# Voltage_conversion.net
KiCad netlist of a schematic drawn in Altium Designer
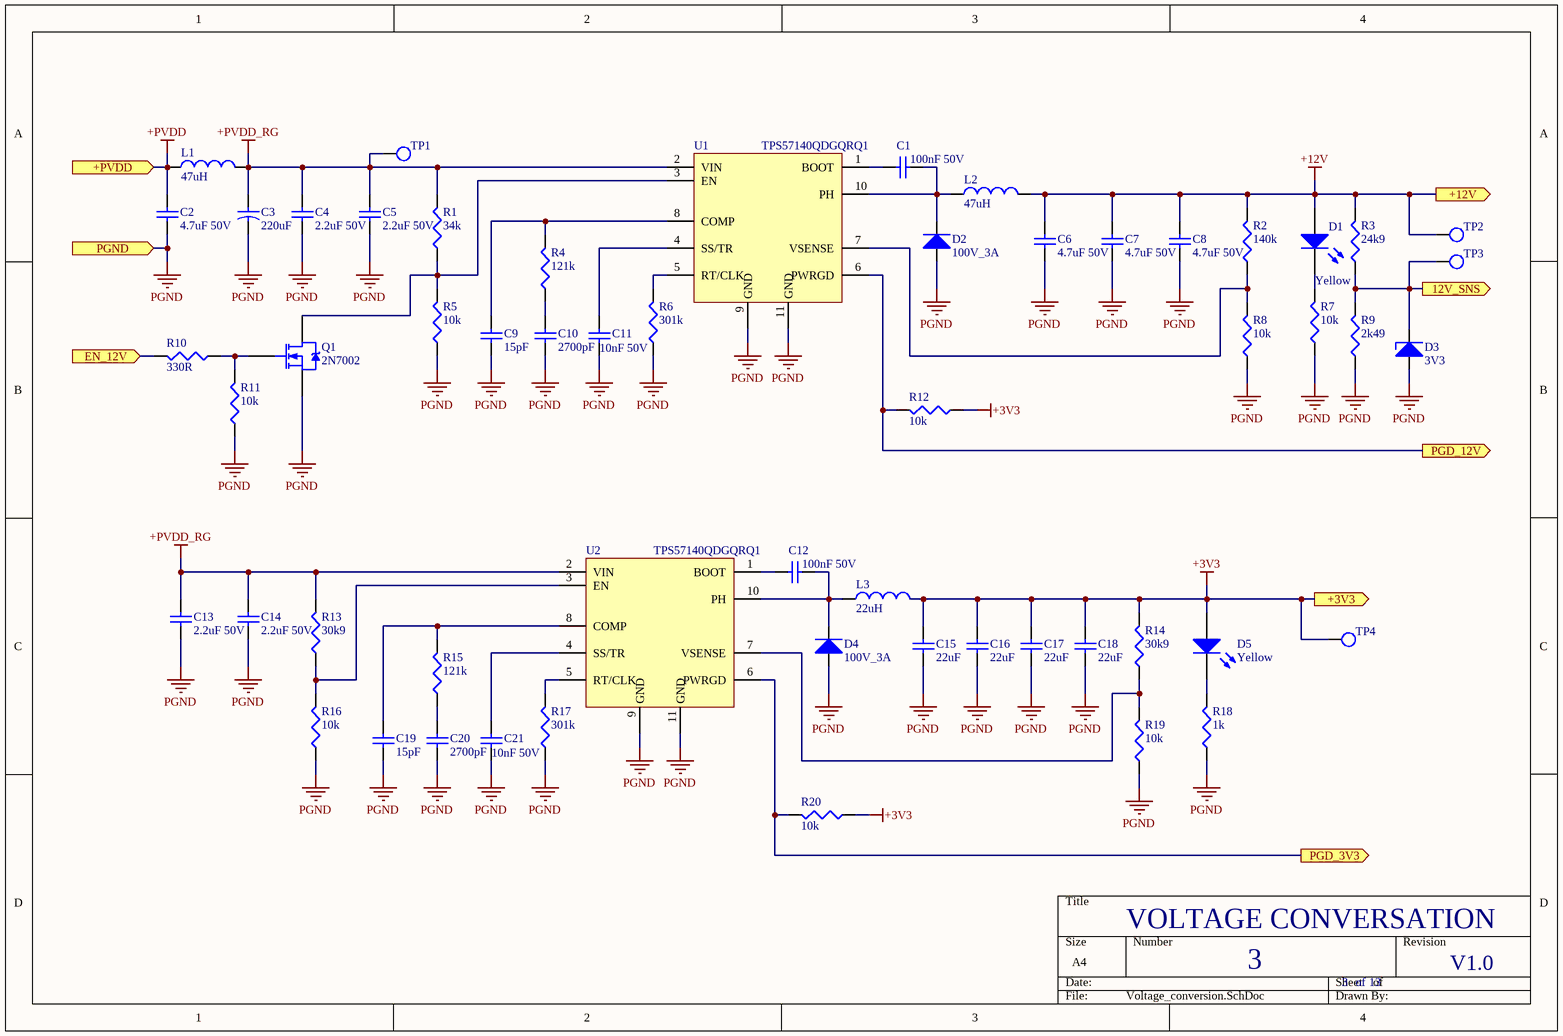
[diagram p0: Voltage_conversion.SchDoc]

(export (version "E")
  (design (tool "Eeschema 10.0.6"))
  (components
    (comp (ref "C1")
      (value "100nF 50V")
      (footprint "CAP0603")
      (description "CAP CER 0.1UF 50V X7R 0603")
      (libsource (lib "CAP_Library") (part "CAP0603_100nF"))
    )
    (comp (ref "C2")
      (value "4.7uF 50V")
      (footprint "CAP1206")
      (description "CAP CER 4.7UF 50V %20 X7R 1206")
      (libsource (lib "CAP_Library") (part "CAP1206_4.7uF"))
    )
    (comp (ref "C3")
      (value "220uF")
      (footprint "CAP_RADIAL_SMD_10x10")
      (description "CAP ALUM 220UF 20% 50V SMD")
      (libsource (lib "CAP_Library") (part "CAP_RADIAL_EEE-FK1H221GP"))
    )
    (comp (ref "C4")
      (value "2.2uF 50V")
      (footprint "CAP1206")
      (description "CAP CER 2.2UF 50V X7R 1206")
      (libsource (lib "CAP_Library") (part "CAP1206_2.2uF_50V"))
    )
    (comp (ref "C5")
      (value "2.2uF 50V")
      (footprint "CAP1206")
      (description "CAP CER 2.2UF 50V X7R 1206")
      (libsource (lib "CAP_Library") (part "CAP1206_2.2uF_50V"))
    )
    (comp (ref "C6")
      (value "4.7uF 50V")
      (footprint "CAP1206")
      (description "CAP CER 4.7UF 50V %20 X7R 1206")
      (libsource (lib "CAP_Library") (part "CAP1206_4.7uF"))
    )
    (comp (ref "C7")
      (value "4.7uF 50V")
      (footprint "CAP1206")
      (description "CAP CER 4.7UF 50V %20 X7R 1206")
      (libsource (lib "CAP_Library") (part "CAP1206_4.7uF"))
    )
    (comp (ref "C8")
      (value "4.7uF 50V")
      (footprint "CAP1206")
      (description "CAP CER 4.7UF 50V %20 X7R 1206")
      (libsource (lib "CAP_Library") (part "CAP1206_4.7uF"))
    )
    (comp (ref "C9")
      (value "15pF")
      (footprint "CAP0603")
      (description "CAP CER 15PF 50V C0G/NP0 0603")
      (libsource (lib "CAP_Library") (part "CAP0603_15pF"))
    )
    (comp (ref "C10")
      (value "2700pF")
      (footprint "CAP0603")
      (description "CAP CER 1200PF 50V X7R 0603")
      (libsource (lib "CAP_Library") (part "CAP0603_2700pF"))
    )
    (comp (ref "C11")
      (value "10nF 50V")
      (footprint "CAP0603")
      (description "CAP CER 10nF 50V X7R 0603")
      (libsource (lib "CAP_Library") (part "CAP0603_10nF"))
    )
    (comp (ref "C12")
      (value "100nF 50V")
      (footprint "CAP0603")
      (description "CAP CER 0.1UF 50V X7R 0603")
      (libsource (lib "CAP_Library") (part "CAP0603_100nF"))
    )
    (comp (ref "C13")
      (value "2.2uF 50V")
      (footprint "CAP1206")
      (description "CAP CER 2.2UF 50V X7R 1206")
      (libsource (lib "CAP_Library") (part "CAP1206_2.2uF_50V"))
    )
    (comp (ref "C14")
      (value "2.2uF 50V")
      (footprint "CAP1206")
      (description "CAP CER 2.2UF 50V X7R 1206")
      (libsource (lib "CAP_Library") (part "CAP1206_2.2uF_50V"))
    )
    (comp (ref "C15")
      (value "22uF")
      (footprint "CAP1206")
      (description "CAP CER 22UF 16V X6S 1206")
      (libsource (lib "CAP_Library") (part "CAP1206_22uF_16V"))
    )
    (comp (ref "C16")
      (value "22uF")
      (footprint "CAP1206")
      (description "CAP CER 22UF 16V X6S 1206")
      (libsource (lib "CAP_Library") (part "CAP1206_22uF_16V"))
    )
    (comp (ref "C17")
      (value "22uF")
      (footprint "CAP1206")
      (description "CAP CER 22UF 16V X6S 1206")
      (libsource (lib "CAP_Library") (part "CAP1206_22uF_16V"))
    )
    (comp (ref "C18")
      (value "22uF")
      (footprint "CAP1206")
      (description "CAP CER 22UF 16V X6S 1206")
      (libsource (lib "CAP_Library") (part "CAP1206_22uF_16V"))
    )
    (comp (ref "C19")
      (value "15pF")
      (footprint "CAP0603")
      (description "CAP CER 15PF 50V C0G/NP0 0603")
      (libsource (lib "CAP_Library") (part "CAP0603_15pF"))
    )
    (comp (ref "C20")
      (value "2700pF")
      (footprint "CAP0603")
      (description "CAP CER 1200PF 50V X7R 0603")
      (libsource (lib "CAP_Library") (part "CAP0603_2700pF"))
    )
    (comp (ref "C21")
      (value "10nF 50V")
      (footprint "CAP0603")
      (description "CAP CER 10nF 50V X7R 0603")
      (libsource (lib "CAP_Library") (part "CAP0603_10nF"))
    )
    (comp (ref "D1")
      (value "Yellow")
      (footprint "LED0603")
      (description "LED YELLOW CLEAR 0603 SMD")
      (libsource (lib "MISC_Library") (part "LED0603_YELLOW"))
    )
    (comp (ref "D2")
      (value "100V_3A")
      (footprint "DO-221A")
      (description "DIODE FRED 100V 3A DO-221AD")
      (libsource (lib "DIODE_Library") (part "FRED_VS-3EYH01-M3/H_100V_3A"))
    )
    (comp (ref "D3")
      (value "3V3")
      (footprint "SOD323")
      (description "DIODE ZENER 3.3V 300MW SOD323")
      (libsource (lib "DIODE_Library") (part "ZENER_3V3_MM3Z3V3T1G"))
    )
    (comp (ref "D4")
      (value "100V_3A")
      (footprint "DO-221A")
      (description "DIODE FRED 100V 3A DO-221AD")
      (libsource (lib "DIODE_Library") (part "FRED_VS-3EYH01-M3/H_100V_3A"))
    )
    (comp (ref "D5")
      (value "Yellow")
      (footprint "LED0603")
      (description "LED YELLOW CLEAR 0603 SMD")
      (libsource (lib "MISC_Library") (part "LED0603_YELLOW"))
    )
    (comp (ref "L1")
      (value "47uH")
      (footprint "IND_SRR1208")
      (description "FIXED IND 47UH 2.9A 80 MOHM SMD")
      (libsource (lib "IND_Library") (part "IND_SRR1280-470M"))
    )
    (comp (ref "L2")
      (value "47uH")
      (footprint "IND_SRR1208")
      (description "FIXED IND 47UH 2.9A 80 MOHM SMD")
      (libsource (lib "IND_Library") (part "IND_SRR1280-470M"))
    )
    (comp (ref "L3")
      (value "22uH")
      (footprint "IND_VLS")
      (description "FIXED IND 22UH 1.9A 105MOHM SMD")
      (libsource (lib "IND_Library") (part "IND_VLS6045EX-220M-H"))
    )
    (comp (ref "Q1")
      (value "2N7002")
      (footprint "SOT23_2N7002")
      (description "MOSFET N-CH 60V 0.36A SOT-23")
      (libsource (lib "Mosfet_Library") (part "2N7002P,215_NMOS_60V"))
    )
    (comp (ref "R1")
      (value "34k")
      (footprint "RES0603")
      (description "RES SMD 34K OHM 1% 1/10W 0603")
      (libsource (lib "RES_Library") (part "RES0603_34k"))
    )
    (comp (ref "R2")
      (value "140k")
      (footprint "RES0603")
      (description "RES 1470 OHM 1% 1/10W 0603")
      (libsource (lib "RES_Library") (part "RES0603_140k"))
    )
    (comp (ref "R3")
      (value "24k9")
      (footprint "RES0603")
      (description "RES SMD 24.9K OHM 1% 1/10W 0603")
      (libsource (lib "RES_Library") (part "RES0603_24k9"))
    )
    (comp (ref "R4")
      (value "121k")
      (footprint "RES0603")
      (description "RES 121K OHM 1% 1/10W 0603")
      (libsource (lib "RES_Library") (part "RES0603_121k"))
    )
    (comp (ref "R5")
      (value "10k")
      (footprint "RES0603")
      (description "RES SMD 10K OHM 5% 1/10W 0603")
      (libsource (lib "RES_Library") (part "RES0603_10k"))
    )
    (comp (ref "R6")
      (value "301k")
      (footprint "RES0603")
      (description "RES SMD 301K OHM 1% 1/10W 0603")
      (libsource (lib "RES_Library") (part "RES0603_301k"))
    )
    (comp (ref "R7")
      (value "10k")
      (footprint "RES0603")
      (description "RES SMD 10K OHM 5% 1/10W 0603")
      (libsource (lib "RES_Library") (part "RES0603_10k"))
    )
    (comp (ref "R8")
      (value "10k")
      (footprint "RES0603")
      (description "RES SMD 10K OHM 5% 1/10W 0603")
      (libsource (lib "RES_Library") (part "RES0603_10k"))
    )
    (comp (ref "R9")
      (value "2k49")
      (footprint "RES0603")
      (description "RES 2.49K OHM 1% 1/10W 0603")
      (libsource (lib "RES_Library") (part "RES0603_2k49"))
    )
    (comp (ref "R10")
      (value "330R")
      (footprint "RES0603")
      (description "RES 330 OHM 1% 1/10W 0603")
      (libsource (lib "RES_Library") (part "RES0603_330R"))
    )
    (comp (ref "R11")
      (value "10k")
      (footprint "RES0603")
      (description "RES SMD 10K OHM 5% 1/10W 0603")
      (libsource (lib "RES_Library") (part "RES0603_10k"))
    )
    (comp (ref "R12")
      (value "10k")
      (footprint "RES0603")
      (description "RES SMD 10K OHM 5% 1/10W 0603")
      (libsource (lib "RES_Library") (part "RES0603_10k"))
    )
    (comp (ref "R13")
      (value "30k9")
      (footprint "RES0603")
      (description "RES SMD 30K9 OHM 1% 1/10W 0603")
      (libsource (lib "RES_Library") (part "RES0603_30k9"))
    )
    (comp (ref "R14")
      (value "30k9")
      (footprint "RES0603")
      (description "RES SMD 30K9 OHM 1% 1/10W 0603")
      (libsource (lib "RES_Library") (part "RES0603_30k9"))
    )
    (comp (ref "R15")
      (value "121k")
      (footprint "RES0603")
      (description "RES 121K OHM 1% 1/10W 0603")
      (libsource (lib "RES_Library") (part "RES0603_121k"))
    )
    (comp (ref "R16")
      (value "10k")
      (footprint "RES0603")
      (description "RES SMD 10K OHM 5% 1/10W 0603")
      (libsource (lib "RES_Library") (part "RES0603_10k"))
    )
    (comp (ref "R17")
      (value "301k")
      (footprint "RES0603")
      (description "RES SMD 301K OHM 1% 1/10W 0603")
      (libsource (lib "RES_Library") (part "RES0603_301k"))
    )
    (comp (ref "R18")
      (value "1k")
      (footprint "RES0603")
      (description "RES SMD 1K OHM 1% 1/10W 0603")
      (libsource (lib "RES_Library") (part "RES0603_1k"))
    )
    (comp (ref "R19")
      (value "10k")
      (footprint "RES0603")
      (description "RES SMD 10K OHM 5% 1/10W 0603")
      (libsource (lib "RES_Library") (part "RES0603_10k"))
    )
    (comp (ref "R20")
      (value "10k")
      (footprint "RES0603")
      (description "RES SMD 10K OHM 5% 1/10W 0603")
      (libsource (lib "RES_Library") (part "RES0603_10k"))
    )
    (comp (ref "TP1")
      (value "TEST_POINT")
      (footprint "TEST_POINT_TH")
      (libsource (lib "MISC_Library") (part "TEST_POINT"))
    )
    (comp (ref "TP2")
      (value "TEST_POINT")
      (footprint "TEST_POINT_TH")
      (libsource (lib "MISC_Library") (part "TEST_POINT"))
    )
    (comp (ref "TP3")
      (value "TEST_POINT")
      (footprint "TEST_POINT_TH")
      (libsource (lib "MISC_Library") (part "TEST_POINT"))
    )
    (comp (ref "TP4")
      (value "TEST_POINT")
      (footprint "TEST_POINT_TH")
      (libsource (lib "MISC_Library") (part "TEST_POINT"))
    )
    (comp (ref "U1")
      (value "1.5A")
      (footprint "MSOP_EP")
      (description "IC REG BUCK ADJ 1.5A 10MSOP")
      (fields (field (name "P/N") "TPS57140QDGQRQ1"))
      (libsource (lib "IC_Library") (part "REG_SMPS_TPS57140QDGQRQ1"))
    )
    (comp (ref "U2")
      (value "1.5A")
      (footprint "MSOP_EP")
      (description "IC REG BUCK ADJ 1.5A 10MSOP")
      (fields (field (name "P/N") "TPS57140QDGQRQ1"))
      (libsource (lib "IC_Library") (part "REG_SMPS_TPS57140QDGQRQ1"))
    )
  )
  (nets
    (net (code "1") (name "+3V3") (class "Default")
      (node (ref "C15") (pin "2") (pinfunction "2_2") (pintype "passive"))
      (node (ref "C16") (pin "2") (pinfunction "2_2") (pintype "passive"))
      (node (ref "C17") (pin "2") (pinfunction "2_2") (pintype "passive"))
      (node (ref "C18") (pin "2") (pinfunction "2_2") (pintype "passive"))
      (node (ref "D5") (pin "1") (pinfunction "A_1") (pintype "passive"))
      (node (ref "L3") (pin "2") (pinfunction "2_2") (pintype "passive"))
      (node (ref "R12") (pin "1") (pinfunction "1_1") (pintype "passive"))
      (node (ref "R14") (pin "2") (pinfunction "2_2") (pintype "passive"))
      (node (ref "R20") (pin "1") (pinfunction "1_1") (pintype "passive"))
      (node (ref "TP4") (pin "1") (pinfunction "1_1") (pintype "passive"))
    )
    (net (code "2") (name "+12V") (class "Default")
      (node (ref "C6") (pin "2") (pinfunction "2_2") (pintype "passive"))
      (node (ref "C7") (pin "2") (pinfunction "2_2") (pintype "passive"))
      (node (ref "C8") (pin "2") (pinfunction "2_2") (pintype "passive"))
      (node (ref "D1") (pin "1") (pinfunction "A_1") (pintype "passive"))
      (node (ref "L2") (pin "2") (pinfunction "2_2") (pintype "passive"))
      (node (ref "R2") (pin "2") (pinfunction "2_2") (pintype "passive"))
      (node (ref "R3") (pin "2") (pinfunction "2_2") (pintype "passive"))
      (node (ref "TP2") (pin "1") (pinfunction "1_1") (pintype "passive"))
    )
    (net (code "3") (name "+PVDD") (class "Default")
      (node (ref "C2") (pin "2") (pinfunction "2_2") (pintype "passive"))
      (node (ref "L1") (pin "1") (pinfunction "1_1") (pintype "passive"))
    )
    (net (code "4") (name "+PVDD_RG") (class "Default")
      (node (ref "C13") (pin "2") (pinfunction "2_2") (pintype "passive"))
      (node (ref "C14") (pin "2") (pinfunction "2_2") (pintype "passive"))
      (node (ref "C3") (pin "1") (pinfunction "1_1") (pintype "passive"))
      (node (ref "C4") (pin "2") (pinfunction "2_2") (pintype "passive"))
      (node (ref "C5") (pin "2") (pinfunction "2_2") (pintype "passive"))
      (node (ref "L1") (pin "2") (pinfunction "2_2") (pintype "passive"))
      (node (ref "R1") (pin "2") (pinfunction "2_2") (pintype "passive"))
      (node (ref "R13") (pin "2") (pinfunction "2_2") (pintype "passive"))
      (node (ref "TP1") (pin "1") (pinfunction "1_1") (pintype "passive"))
      (node (ref "U1") (pin "2") (pinfunction "VIN_2") (pintype "passive"))
      (node (ref "U2") (pin "2") (pinfunction "VIN_2") (pintype "passive"))
    )
    (net (code "5") (name "/12V_SNS") (class "Default")
      (node (ref "D3") (pin "1") (pinfunction "K_1") (pintype "passive"))
      (node (ref "R3") (pin "1") (pinfunction "1_1") (pintype "passive"))
      (node (ref "R9") (pin "2") (pinfunction "2_2") (pintype "passive"))
      (node (ref "TP3") (pin "1") (pinfunction "1_1") (pintype "passive"))
    )
    (net (code "6") (name "/EN_12V") (class "Default")
      (node (ref "R10") (pin "2") (pinfunction "2_2") (pintype "passive"))
    )
    (net (code "7") (name "/PGD_3V3") (class "Default")
      (node (ref "R20") (pin "2") (pinfunction "2_2") (pintype "passive"))
      (node (ref "U2") (pin "6") (pinfunction "PWRGD_6") (pintype "passive"))
    )
    (net (code "8") (name "/PGD_12V") (class "Default")
      (node (ref "R12") (pin "2") (pinfunction "2_2") (pintype "passive"))
      (node (ref "U1") (pin "6") (pinfunction "PWRGD_6") (pintype "passive"))
    )
    (net (code "9") (name "Net-(C10-Pad2)") (class "Default")
      (node (ref "C10") (pin "2") (pinfunction "2_2") (pintype "passive"))
      (node (ref "R4") (pin "1") (pinfunction "1_1") (pintype "passive"))
    )
    (net (code "10") (name "Net-(C20-Pad2)") (class "Default")
      (node (ref "C20") (pin "2") (pinfunction "2_2") (pintype "passive"))
      (node (ref "R15") (pin "1") (pinfunction "1_1") (pintype "passive"))
    )
    (net (code "11") (name "Net-(D1-K)") (class "Default")
      (node (ref "D1") (pin "2") (pinfunction "K_2") (pintype "passive"))
      (node (ref "R7") (pin "2") (pinfunction "2_2") (pintype "passive"))
    )
    (net (code "12") (name "Net-(D2-K)") (class "Default")
      (node (ref "C1") (pin "1") (pinfunction "1_1") (pintype "passive"))
      (node (ref "D2") (pin "1") (pinfunction "K_1") (pintype "passive"))
      (node (ref "L2") (pin "1") (pinfunction "1_1") (pintype "passive"))
      (node (ref "U1") (pin "10") (pinfunction "PH_10") (pintype "passive"))
    )
    (net (code "13") (name "Net-(D4-K)") (class "Default")
      (node (ref "C12") (pin "1") (pinfunction "1_1") (pintype "passive"))
      (node (ref "D4") (pin "1") (pinfunction "K_1") (pintype "passive"))
      (node (ref "L3") (pin "1") (pinfunction "1_1") (pintype "passive"))
      (node (ref "U2") (pin "10") (pinfunction "PH_10") (pintype "passive"))
    )
    (net (code "14") (name "Net-(D5-K)") (class "Default")
      (node (ref "D5") (pin "2") (pinfunction "K_2") (pintype "passive"))
      (node (ref "R18") (pin "2") (pinfunction "2_2") (pintype "passive"))
    )
    (net (code "15") (name "Net-(Q1-D)") (class "Default")
      (node (ref "Q1") (pin "3") (pinfunction "D_3") (pintype "passive"))
      (node (ref "R1") (pin "1") (pinfunction "1_1") (pintype "passive"))
      (node (ref "R5") (pin "2") (pinfunction "2_2") (pintype "passive"))
      (node (ref "U1") (pin "3") (pinfunction "EN_3") (pintype "passive"))
    )
    (net (code "16") (name "Net-(Q1-G)") (class "Default")
      (node (ref "Q1") (pin "1") (pinfunction "G_1") (pintype "passive"))
      (node (ref "R10") (pin "1") (pinfunction "1_1") (pintype "passive"))
      (node (ref "R11") (pin "2") (pinfunction "2_2") (pintype "passive"))
    )
    (net (code "17") (name "Net-(U1-BOOT)") (class "Default")
      (node (ref "C1") (pin "2") (pinfunction "2_2") (pintype "passive"))
      (node (ref "U1") (pin "1") (pinfunction "BOOT_1") (pintype "passive"))
    )
    (net (code "18") (name "Net-(U1-COMP)") (class "Default")
      (node (ref "C9") (pin "2") (pinfunction "2_2") (pintype "passive"))
      (node (ref "R4") (pin "2") (pinfunction "2_2") (pintype "passive"))
      (node (ref "U1") (pin "8") (pinfunction "COMP_8") (pintype "passive"))
    )
    (net (code "19") (name "Net-(U1-RT{slash}CLK)") (class "Default")
      (node (ref "R6") (pin "2") (pinfunction "2_2") (pintype "passive"))
      (node (ref "U1") (pin "5") (pinfunction "RT/CLK_5") (pintype "passive"))
    )
    (net (code "20") (name "Net-(U1-SS{slash}TR)") (class "Default")
      (node (ref "C11") (pin "2") (pinfunction "2_2") (pintype "passive"))
      (node (ref "U1") (pin "4") (pinfunction "SS/TR_4") (pintype "passive"))
    )
    (net (code "21") (name "Net-(U1-VSENSE)") (class "Default")
      (node (ref "R2") (pin "1") (pinfunction "1_1") (pintype "passive"))
      (node (ref "R8") (pin "2") (pinfunction "2_2") (pintype "passive"))
      (node (ref "U1") (pin "7") (pinfunction "VSENSE_7") (pintype "passive"))
    )
    (net (code "22") (name "Net-(U2-BOOT)") (class "Default")
      (node (ref "C12") (pin "2") (pinfunction "2_2") (pintype "passive"))
      (node (ref "U2") (pin "1") (pinfunction "BOOT_1") (pintype "passive"))
    )
    (net (code "23") (name "Net-(U2-COMP)") (class "Default")
      (node (ref "C19") (pin "2") (pinfunction "2_2") (pintype "passive"))
      (node (ref "R15") (pin "2") (pinfunction "2_2") (pintype "passive"))
      (node (ref "U2") (pin "8") (pinfunction "COMP_8") (pintype "passive"))
    )
    (net (code "24") (name "Net-(U2-EN)") (class "Default")
      (node (ref "R13") (pin "1") (pinfunction "1_1") (pintype "passive"))
      (node (ref "R16") (pin "2") (pinfunction "2_2") (pintype "passive"))
      (node (ref "U2") (pin "3") (pinfunction "EN_3") (pintype "passive"))
    )
    (net (code "25") (name "Net-(U2-RT{slash}CLK)") (class "Default")
      (node (ref "R17") (pin "2") (pinfunction "2_2") (pintype "passive"))
      (node (ref "U2") (pin "5") (pinfunction "RT/CLK_5") (pintype "passive"))
    )
    (net (code "26") (name "Net-(U2-SS{slash}TR)") (class "Default")
      (node (ref "C21") (pin "2") (pinfunction "2_2") (pintype "passive"))
      (node (ref "U2") (pin "4") (pinfunction "SS/TR_4") (pintype "passive"))
    )
    (net (code "27") (name "Net-(U2-VSENSE)") (class "Default")
      (node (ref "R14") (pin "1") (pinfunction "1_1") (pintype "passive"))
      (node (ref "R19") (pin "2") (pinfunction "2_2") (pintype "passive"))
      (node (ref "U2") (pin "7") (pinfunction "VSENSE_7") (pintype "passive"))
    )
    (net (code "28") (name "PGND") (class "Default")
      (node (ref "C10") (pin "1") (pinfunction "1_1") (pintype "passive"))
      (node (ref "C11") (pin "1") (pinfunction "1_1") (pintype "passive"))
      (node (ref "C13") (pin "1") (pinfunction "1_1") (pintype "passive"))
      (node (ref "C14") (pin "1") (pinfunction "1_1") (pintype "passive"))
      (node (ref "C15") (pin "1") (pinfunction "1_1") (pintype "passive"))
      (node (ref "C16") (pin "1") (pinfunction "1_1") (pintype "passive"))
      (node (ref "C17") (pin "1") (pinfunction "1_1") (pintype "passive"))
      (node (ref "C18") (pin "1") (pinfunction "1_1") (pintype "passive"))
      (node (ref "C19") (pin "1") (pinfunction "1_1") (pintype "passive"))
      (node (ref "C2") (pin "1") (pinfunction "1_1") (pintype "passive"))
      (node (ref "C20") (pin "1") (pinfunction "1_1") (pintype "passive"))
      (node (ref "C21") (pin "1") (pinfunction "1_1") (pintype "passive"))
      (node (ref "C3") (pin "2") (pinfunction "2_2") (pintype "passive"))
      (node (ref "C4") (pin "1") (pinfunction "1_1") (pintype "passive"))
      (node (ref "C5") (pin "1") (pinfunction "1_1") (pintype "passive"))
      (node (ref "C6") (pin "1") (pinfunction "1_1") (pintype "passive"))
      (node (ref "C7") (pin "1") (pinfunction "1_1") (pintype "passive"))
      (node (ref "C8") (pin "1") (pinfunction "1_1") (pintype "passive"))
      (node (ref "C9") (pin "1") (pinfunction "1_1") (pintype "passive"))
      (node (ref "D2") (pin "2") (pinfunction "A_2") (pintype "passive"))
      (node (ref "D3") (pin "2") (pinfunction "A_2") (pintype "passive"))
      (node (ref "D4") (pin "2") (pinfunction "A_2") (pintype "passive"))
      (node (ref "Q1") (pin "2") (pinfunction "S_2") (pintype "passive"))
      (node (ref "R11") (pin "1") (pinfunction "1_1") (pintype "passive"))
      (node (ref "R16") (pin "1") (pinfunction "1_1") (pintype "passive"))
      (node (ref "R17") (pin "1") (pinfunction "1_1") (pintype "passive"))
      (node (ref "R18") (pin "1") (pinfunction "1_1") (pintype "passive"))
      (node (ref "R19") (pin "1") (pinfunction "1_1") (pintype "passive"))
      (node (ref "R5") (pin "1") (pinfunction "1_1") (pintype "passive"))
      (node (ref "R6") (pin "1") (pinfunction "1_1") (pintype "passive"))
      (node (ref "R7") (pin "1") (pinfunction "1_1") (pintype "passive"))
      (node (ref "R8") (pin "1") (pinfunction "1_1") (pintype "passive"))
      (node (ref "R9") (pin "1") (pinfunction "1_1") (pintype "passive"))
      (node (ref "U1") (pin "11") (pinfunction "GND_11") (pintype "passive"))
      (node (ref "U1") (pin "9") (pinfunction "GND_9") (pintype "passive"))
      (node (ref "U2") (pin "11") (pinfunction "GND_11") (pintype "passive"))
      (node (ref "U2") (pin "9") (pinfunction "GND_9") (pintype "passive"))
    )
  )
)
